# 100068622_block_diagram.net
KiCad netlist of a schematic drawn in Altium Designer
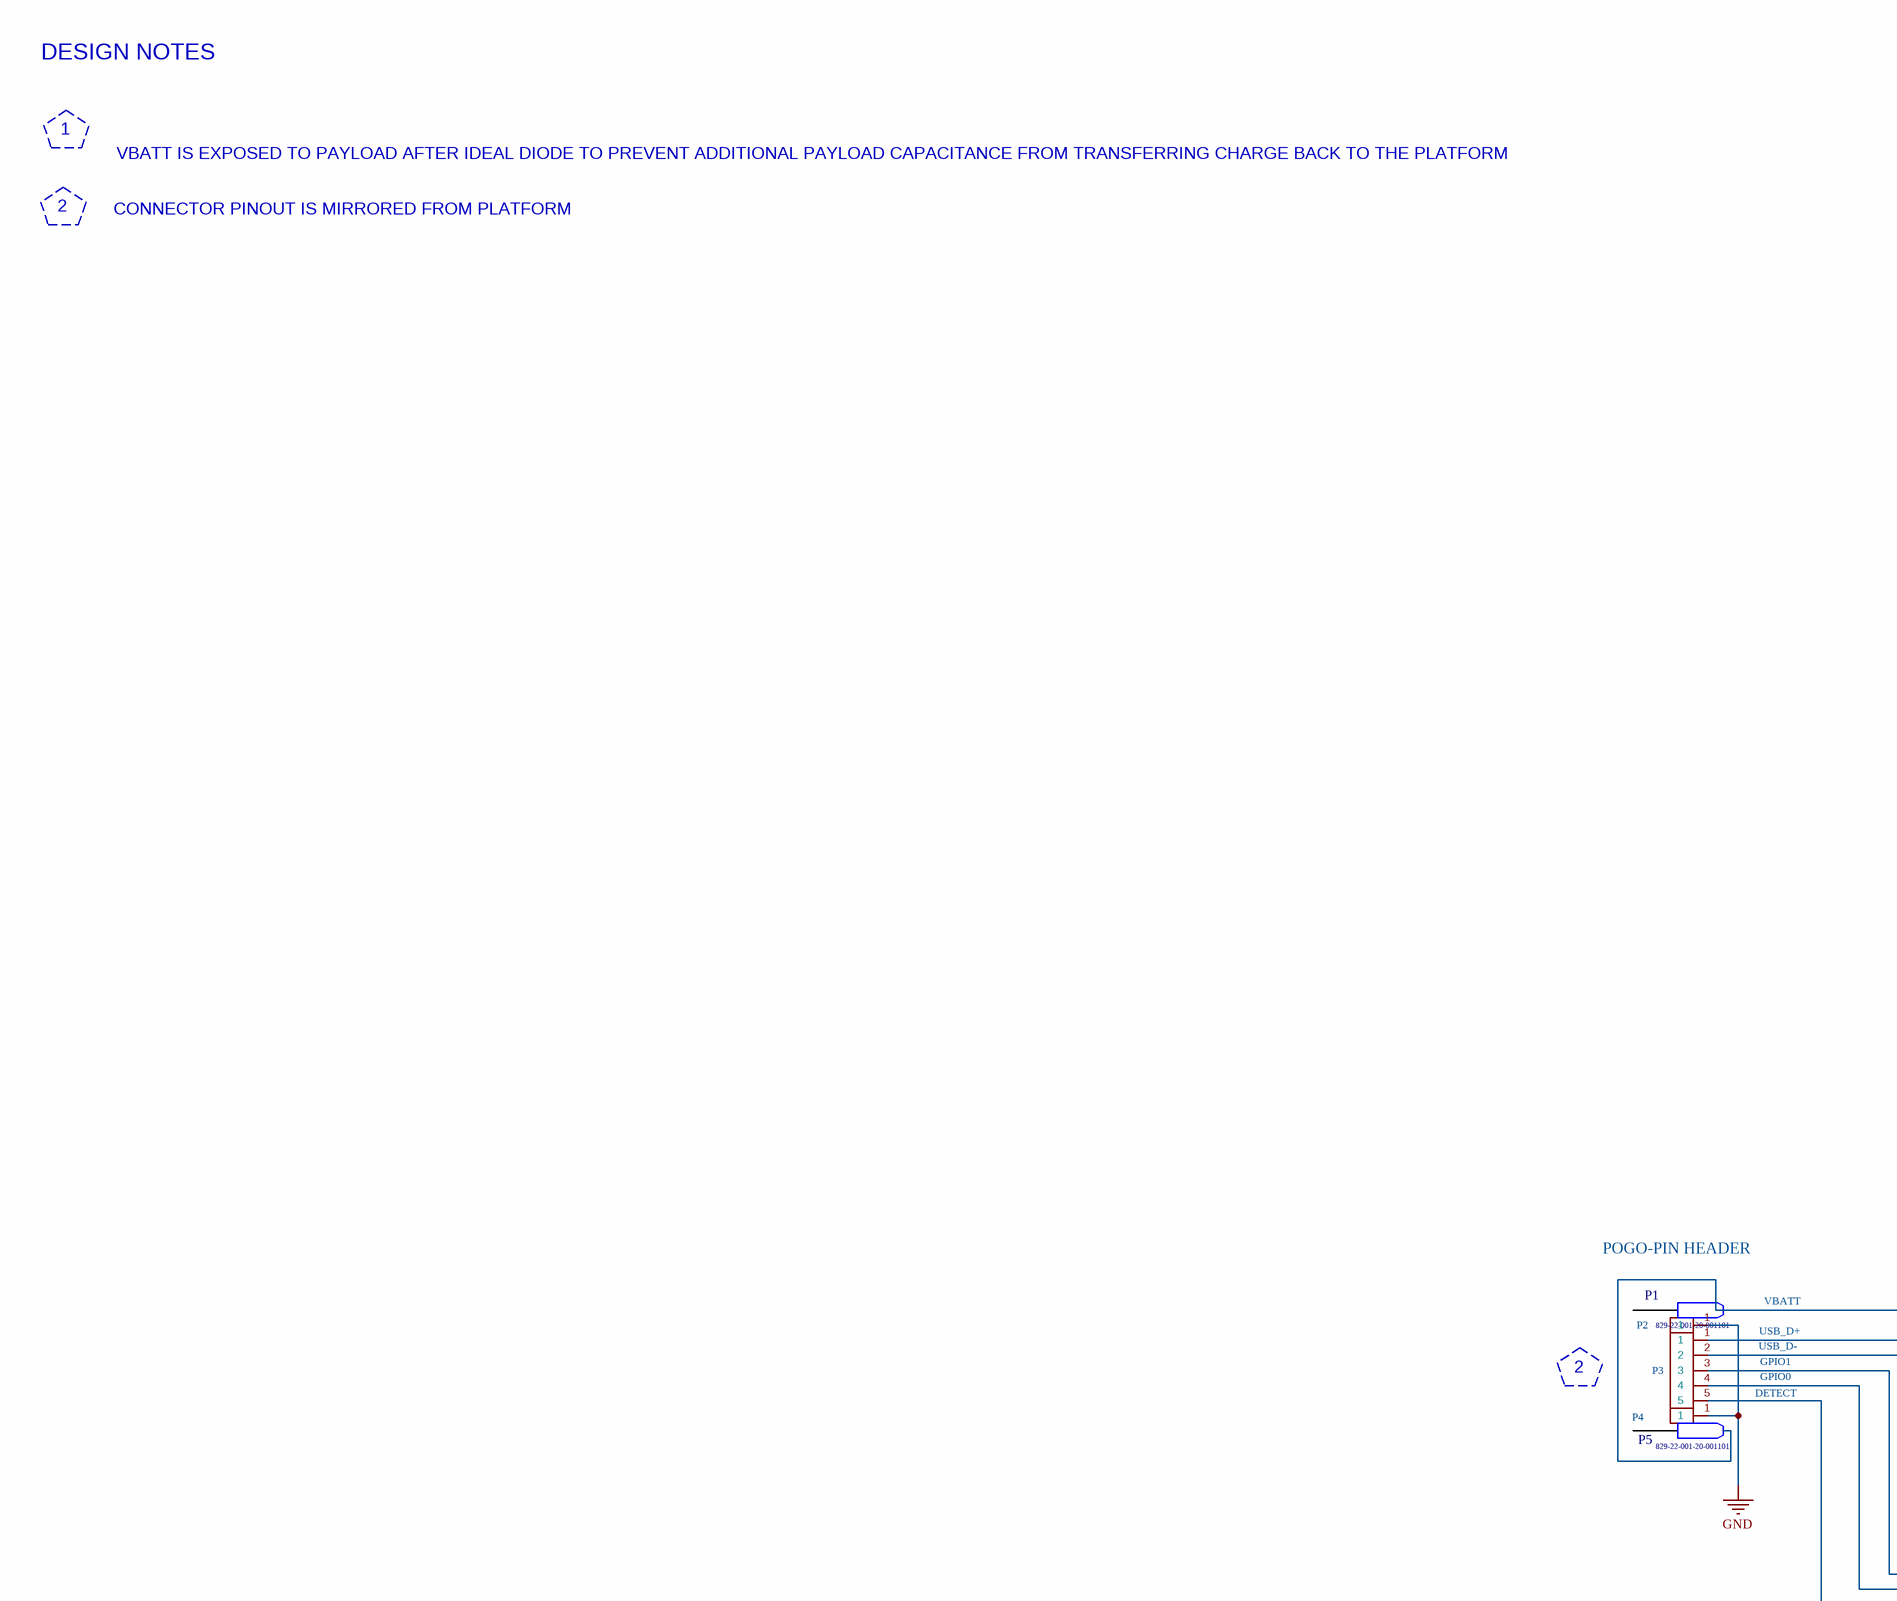
[diagram p0: 100068622_block_diagram.SchDoc, left]
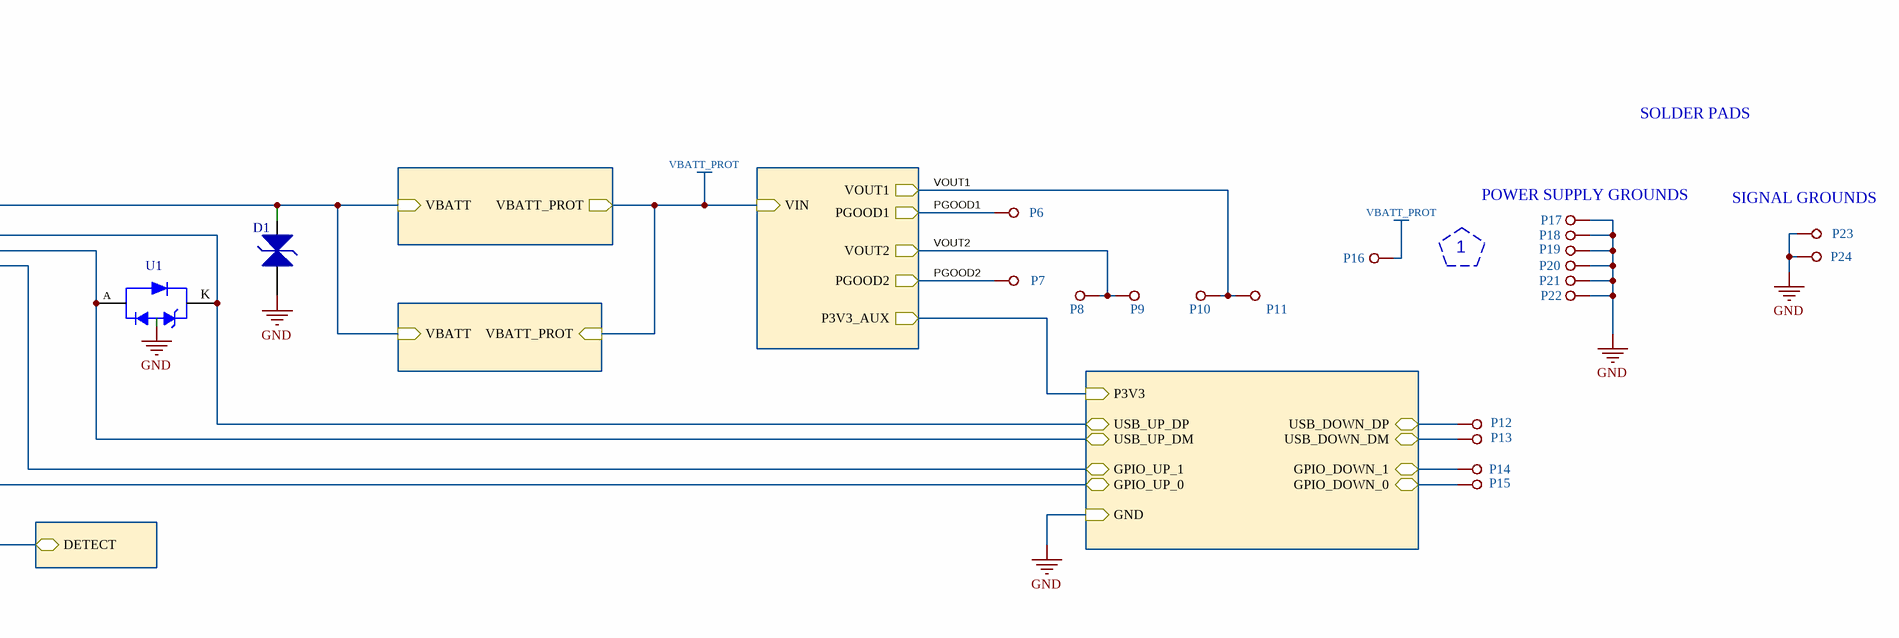
[diagram p1: 100068622_block_diagram.SchDoc, right]

(export (version "E")
  (design (tool "Eeschema 10.0.6"))
  (components
    (comp (ref "D1")
      (value "SMF26A")
      (footprint "DI-SOD123F-A")
      (description "SMF Series 200 W 26 V Uni-Directional Surface Mount TVS Diode - SOD-123F")
      (libsource (lib "Picatinny Server") (part "Diode - Bidirectional"))
    )
    (comp (ref "P1")
      (value "~")
      (footprint "829-22-001-20-001101-Footprint-1")
      (description "Conn Spring Loaded Connector HDR 1 POS Solder RA Thru-Hole 1.14mm MidStroke")
      (libsource (lib "Picatinny Server") (part "Mill Max 4914-0-00-15-00-00-03-0-Symbol-1"))
    )
    (comp (ref "P2")
      (value "~")
      (footprint "829-22-001-20-002101")
      (fields (field (name "MPN") "829-22-001-20-002101") (field (name "MANUFACTURER") "Mill-Max"))
      (libsource (lib "1a_MillMax") (part "829-22-001-20-002101"))
    )
    (comp (ref "P3")
      (value "~")
      (footprint "829-22-005-20-001101")
      (fields (field (name "MPN") "829-22-005-20-001101") (field (name "MANUFACTURER") "Mill-Max"))
      (libsource (lib "1a_MillMax") (part "829-22-005-20-001101"))
    )
    (comp (ref "P4")
      (value "~")
      (footprint "829-22-001-20-002101")
      (fields (field (name "MPN") "829-22-001-20-002101") (field (name "MANUFACTURER") "Mill-Max"))
      (libsource (lib "1a_MillMax") (part "829-22-001-20-002101"))
    )
    (comp (ref "P5")
      (value "~")
      (footprint "829-22-001-20-001101-Footprint-1")
      (description "Conn Spring Loaded Connector HDR 1 POS Solder RA Thru-Hole 1.14mm MidStroke")
      (libsource (lib "Picatinny Server") (part "Mill Max 4914-0-00-15-00-00-03-0-Symbol-1"))
    )
    (comp (ref "P6")
      (value "~")
      (footprint "Hand_Solder_Pad_100x80_mil")
      (libsource (lib "1a_Misc") (part "Hand_Solder_Pad_100x80_mil"))
    )
    (comp (ref "P7")
      (value "~")
      (footprint "Hand_Solder_Pad_100x80_mil")
      (libsource (lib "1a_Misc") (part "Hand_Solder_Pad_100x80_mil"))
    )
    (comp (ref "P8")
      (value "~")
      (footprint "Hand_Solder_Pad_100x80_mil")
      (libsource (lib "1a_Misc") (part "Hand_Solder_Pad_100x80_mil"))
    )
    (comp (ref "P9")
      (value "~")
      (footprint "Hand_Solder_Pad_100x80_mil")
      (libsource (lib "1a_Misc") (part "Hand_Solder_Pad_100x80_mil"))
    )
    (comp (ref "P10")
      (value "~")
      (footprint "Hand_Solder_Pad_100x80_mil")
      (libsource (lib "1a_Misc") (part "Hand_Solder_Pad_100x80_mil"))
    )
    (comp (ref "P11")
      (value "~")
      (footprint "Hand_Solder_Pad_100x80_mil")
      (libsource (lib "1a_Misc") (part "Hand_Solder_Pad_100x80_mil"))
    )
    (comp (ref "P12")
      (value "~")
      (footprint "Hand_Solder_Pad_100x80_mil")
      (libsource (lib "1a_Misc") (part "Hand_Solder_Pad_100x80_mil"))
    )
    (comp (ref "P13")
      (value "~")
      (footprint "Hand_Solder_Pad_100x80_mil")
      (libsource (lib "1a_Misc") (part "Hand_Solder_Pad_100x80_mil"))
    )
    (comp (ref "P14")
      (value "~")
      (footprint "Hand_Solder_Pad_100x80_mil")
      (libsource (lib "1a_Misc") (part "Hand_Solder_Pad_100x80_mil"))
    )
    (comp (ref "P15")
      (value "~")
      (footprint "Hand_Solder_Pad_100x80_mil")
      (libsource (lib "1a_Misc") (part "Hand_Solder_Pad_100x80_mil"))
    )
    (comp (ref "P16")
      (value "~")
      (footprint "Hand_Solder_Pad_200x150_mil")
      (libsource (lib "1a_Misc") (part "Hand_Solder_Pad_200x100_mil"))
    )
    (comp (ref "P17")
      (value "~")
      (footprint "Hand_Solder_Pad_100x80_mil")
      (libsource (lib "1a_Misc") (part "Hand_Solder_Pad_100x80_mil"))
    )
    (comp (ref "P18")
      (value "~")
      (footprint "Hand_Solder_Pad_100x80_mil")
      (libsource (lib "1a_Misc") (part "Hand_Solder_Pad_100x80_mil"))
    )
    (comp (ref "P19")
      (value "~")
      (footprint "Hand_Solder_Pad_100x80_mil")
      (libsource (lib "1a_Misc") (part "Hand_Solder_Pad_100x80_mil"))
    )
    (comp (ref "P20")
      (value "~")
      (footprint "Hand_Solder_Pad_100x80_mil")
      (libsource (lib "1a_Misc") (part "Hand_Solder_Pad_100x80_mil"))
    )
    (comp (ref "P21")
      (value "~")
      (footprint "Hand_Solder_Pad_100x80_mil")
      (libsource (lib "1a_Misc") (part "Hand_Solder_Pad_100x80_mil"))
    )
    (comp (ref "P22")
      (value "~")
      (footprint "Hand_Solder_Pad_200x150_mil")
      (libsource (lib "1a_Misc") (part "Hand_Solder_Pad_200x100_mil"))
    )
    (comp (ref "P23")
      (value "~")
      (footprint "Hand_Solder_Pad_100x80_mil")
      (libsource (lib "1a_Misc") (part "Hand_Solder_Pad_100x80_mil"))
    )
    (comp (ref "P24")
      (value "~")
      (footprint "Hand_Solder_Pad_100x80_mil")
      (libsource (lib "1a_Misc") (part "Hand_Solder_Pad_100x80_mil"))
    )
    (comp (ref "U1")
      (value "PESD5V0C2UM")
      (footprint "IC-SOT883-2-B")
      (description "Extremely low capacitance unidirectional ESD protection diode array")
      (libsource (lib "Picatinny Server") (part "Diode - TVS (Unidirectional)"))
    )
  )
  (nets
    (net (code "1") (name "/DETECT") (class "Default")
      (node (ref "P3") (pin "5") (pinfunction "5_5") (pintype "passive"))
    )
    (net (code "4") (name "/GPIO_DOWN_0") (class "Default")
      (node (ref "P15") (pin "1") (pinfunction "1_1") (pintype "passive"))
    )
    (net (code "5") (name "/GPIO_DOWN_1") (class "Default")
      (node (ref "P14") (pin "1") (pinfunction "1_1") (pintype "passive"))
    )
    (net (code "6") (name "/GPIO_UP_0") (class "Default")
      (node (ref "P3") (pin "4") (pinfunction "4_4") (pintype "passive"))
    )
    (net (code "7") (name "/GPIO_UP_1") (class "Default")
      (node (ref "P3") (pin "3") (pinfunction "3_3") (pintype "passive"))
    )
    (net (code "9") (name "/PGOOD1") (class "Default")
      (node (ref "P6") (pin "1") (pinfunction "1_1") (pintype "passive"))
    )
    (net (code "10") (name "/PGOOD2") (class "Default")
      (node (ref "P7") (pin "1") (pinfunction "1_1") (pintype "passive"))
    )
    (net (code "13") (name "/USB_DOWN_DM") (class "Default")
      (node (ref "P13") (pin "1") (pinfunction "1_1") (pintype "passive"))
    )
    (net (code "14") (name "/USB_DOWN_DP") (class "Default")
      (node (ref "P12") (pin "1") (pinfunction "1_1") (pintype "passive"))
    )
    (net (code "15") (name "/USB_UP_DM") (class "Default")
      (node (ref "P3") (pin "2") (pinfunction "2_2") (pintype "passive"))
      (node (ref "U1") (pin "A") (pinfunction "A_A") (pintype "passive"))
    )
    (net (code "16") (name "/USB_UP_DP") (class "Default")
      (node (ref "P3") (pin "1") (pinfunction "1_1") (pintype "passive"))
      (node (ref "U1") (pin "K") (pinfunction "K_K") (pintype "passive"))
    )
    (net (code "18") (name "/VBATT_1") (class "Default")
      (node (ref "D1") (pin "K") (pinfunction "K_K") (pintype "passive"))
    )
    (net (code "19") (name "/VOUT1") (class "Default")
      (node (ref "P10") (pin "1") (pinfunction "1_1") (pintype "passive"))
      (node (ref "P11") (pin "1") (pinfunction "1_1") (pintype "passive"))
    )
    (net (code "20") (name "/VOUT2") (class "Default")
      (node (ref "P8") (pin "1") (pinfunction "1_1") (pintype "passive"))
      (node (ref "P9") (pin "1") (pinfunction "1_1") (pintype "passive"))
    )
    (net (code "21") (name "GND") (class "Default")
      (node (ref "D1") (pin "A") (pinfunction "A_A") (pintype "passive"))
      (node (ref "P17") (pin "1") (pinfunction "1_1") (pintype "passive"))
      (node (ref "P18") (pin "1") (pinfunction "1_1") (pintype "passive"))
      (node (ref "P19") (pin "1") (pinfunction "1_1") (pintype "passive"))
      (node (ref "P2") (pin "1") (pinfunction "1_1") (pintype "passive"))
      (node (ref "P20") (pin "1") (pinfunction "1_1") (pintype "passive"))
      (node (ref "P21") (pin "1") (pinfunction "1_1") (pintype "passive"))
      (node (ref "P22") (pin "1") (pinfunction "1_1") (pintype "passive"))
      (node (ref "P23") (pin "1") (pinfunction "1_1") (pintype "passive"))
      (node (ref "P24") (pin "1") (pinfunction "1_1") (pintype "passive"))
      (node (ref "P4") (pin "1") (pinfunction "1_1") (pintype "passive"))
    )
    (net (code "22") (name "VBATT_PROT") (class "Default")
      (node (ref "P16") (pin "1") (pinfunction "1_1") (pintype "passive"))
    )
    (net (code "23") (name "unconnected-(P1-Pad0)") (class "Default")
      (node (ref "P1") (pin "0") (pinfunction "0_0") (pintype "passive"))
    )
    (net (code "24") (name "unconnected-(P5-Pad0)") (class "Default")
      (node (ref "P5") (pin "0") (pinfunction "0_0") (pintype "passive"))
    )
  )
)
